# HeartAware_Main.net
KiCad netlist of a schematic drawn in Altium Designer
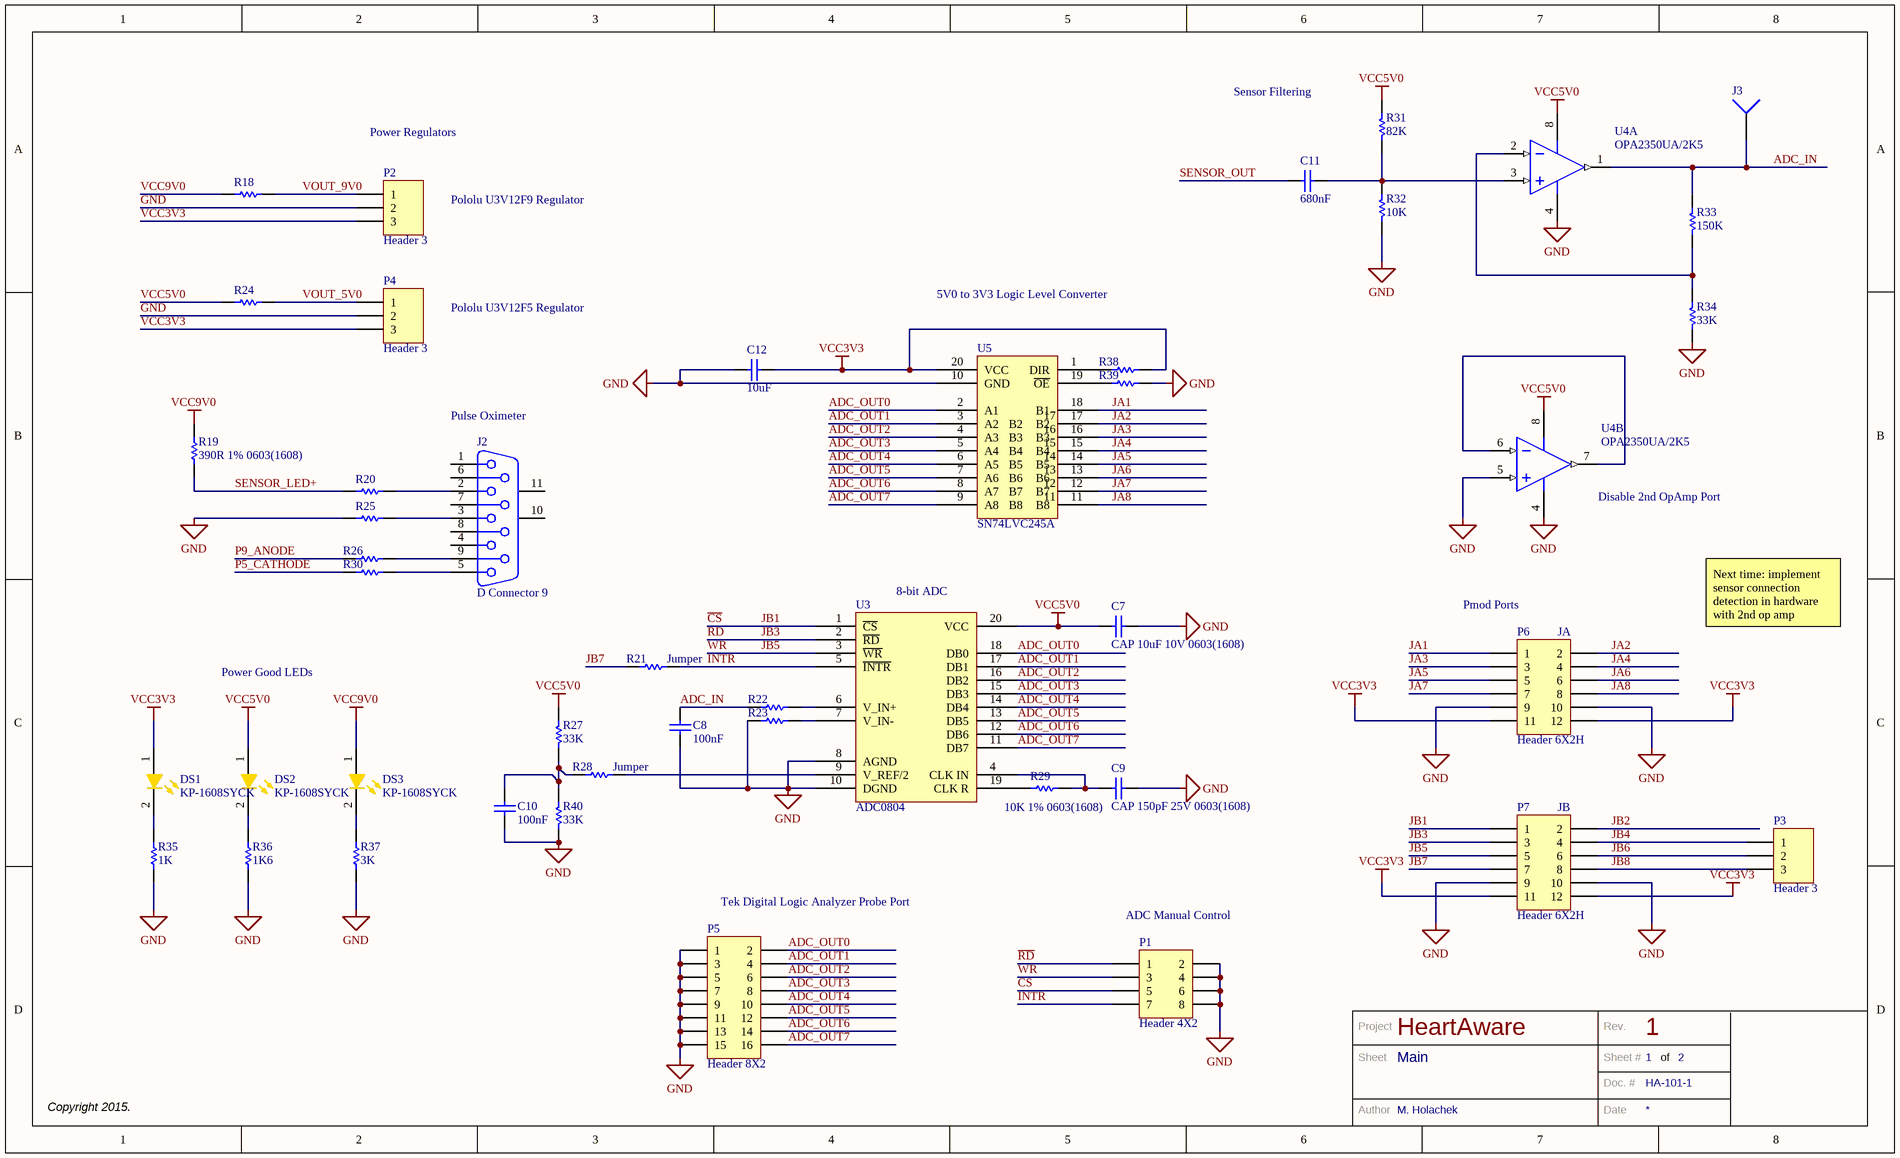
[diagram p0: HeartAware_Main.SchDoc]

(export (version "E")
  (design (tool "Eeschema 10.0.6"))
  (components
    (comp (ref "C7")
      (value "CAP 10uF 10V 0603(1608)")
      (footprint "CAPC0603(1608)100_N")
      (description "CAP 10uF 10V Â±10% 0603 (1608 Metric) Thickness 1mm SMD")
      (fields (field (name "TOLERANCE") "Â±10%"))
      (libsource (lib "Altium Content Vault") (part "CAP"))
    )
    (comp (ref "C8")
      (value "100nF")
      (footprint "CAPC0603(1608)100_M")
      (description "CAP 100nF 25V Â±10% 0603 (1608 Metric) Thickness 1mm SMD")
      (fields (field (name "TOLERANCE") "Â±10%"))
      (libsource (lib "Altium Content Vault") (part "CMP-1035-02588-1"))
    )
    (comp (ref "C9")
      (value "CAP 150pF 25V 0603(1608)")
      (footprint "CAPC0603(1608)100_L")
      (description "CAP 150pF 25V Â±2% 0603 (1608 Metric) Thickness 1mm SMD")
      (fields (field (name "TOLERANCE") "Â±2%"))
      (libsource (lib "Altium Content Vault") (part "CAP"))
    )
    (comp (ref "C10")
      (value "100nF")
      (footprint "CAPC0603(1608)100_M")
      (description "CAP 100nF 25V Â±10% 0603 (1608 Metric) Thickness 1mm SMD")
      (fields (field (name "TOLERANCE") "Â±10%"))
      (libsource (lib "Altium Content Vault") (part "CMP-1035-02588-1"))
    )
    (comp (ref "C11")
      (value "680nF")
      (footprint "CAPC0603(1608)100_N")
      (description "CAP 680nF 25V Â±10% 0603 (1608 Metric) Thickness 1mm SMD")
      (fields (field (name "TOLERANCE") "Â±10%"))
      (libsource (lib "Altium Content Vault") (part "CMP-1035-02722-1"))
    )
    (comp (ref "C12")
      (value "10uF")
      (footprint "CAPC0603(1608)100_N")
      (description "CAP 10uF 10V Â±10% 0603 (1608 Metric) Thickness 1mm SMD")
      (fields (field (name "TOLERANCE") "Â±10%"))
      (libsource (lib "Altium Content Vault") (part "CMP-1035-02799-1"))
    )
    (comp (ref "DS1")
      (value "KP-1608SYCK")
      (footprint "KING-0603LED_YELLOW_V")
      (description "LED, SMT, 0603(1608), 1.1mm thickness, Yellow")
      (fields (field (name "MANUFACTURER") "Kingbright"))
      (libsource (lib "Altium Content Vault") (part "KING-LED-YELLOW-A1K2-2"))
    )
    (comp (ref "DS2")
      (value "KP-1608SYCK")
      (footprint "KING-0603LED_YELLOW_V")
      (description "LED, SMT, 0603(1608), 1.1mm thickness, Yellow")
      (fields (field (name "MANUFACTURER") "Kingbright"))
      (libsource (lib "Altium Content Vault") (part "KING-LED-YELLOW-A1K2-2"))
    )
    (comp (ref "DS3")
      (value "KP-1608SYCK")
      (footprint "KING-0603LED_YELLOW_V")
      (description "LED, SMT, 0603(1608), 1.1mm thickness, Yellow")
      (fields (field (name "MANUFACTURER") "Kingbright"))
      (libsource (lib "Altium Content Vault") (part "KING-LED-YELLOW-A1K2-2"))
    )
    (comp (ref "J2")
      (value "D Connector 9")
      (footprint "DSUB1.385-2H9")
      (description "Receptacle Assembly, 9 Position, Right Angle")
      (fields (field (name "PUBLISHER") "Altium Limited"))
      (libsource (lib "Miscellaneous Connectors") (part "D Connector 9"))
    )
    (comp (ref "J3")
      (value "Socket")
      (footprint "PIN1")
      (fields (field (name "PUBLISHER") "Altium Limited"))
      (libsource (lib "Miscellaneous Connectors") (part "Socket"))
    )
    (comp (ref "P1")
      (value "Header 4X2")
      (footprint "HDR2X4")
      (description "Header, 4-Pin, Dual row")
      (fields (field (name "PUBLISHER") "Altium Limited"))
      (libsource (lib "Miscellaneous Connectors") (part "Header 4X2"))
    )
    (comp (ref "P2")
      (value "Header 3")
      (footprint "HDR1X3")
      (description "Header, 3-Pin")
      (fields (field (name "PUBLISHER") "Altium Limited"))
      (libsource (lib "Miscellaneous Connectors") (part "Header 3"))
    )
    (comp (ref "P3")
      (value "Header 3")
      (footprint "HDR1X3")
      (description "Header, 3-Pin")
      (fields (field (name "PUBLISHER") "Altium Limited"))
      (libsource (lib "Miscellaneous Connectors") (part "Header 3"))
    )
    (comp (ref "P4")
      (value "Header 3")
      (footprint "HDR1X3")
      (description "Header, 3-Pin")
      (fields (field (name "PUBLISHER") "Altium Limited"))
      (libsource (lib "Miscellaneous Connectors") (part "Header 3"))
    )
    (comp (ref "P5")
      (value "Header 8X2")
      (footprint "HDR2X8")
      (description "Header, 8-Pin, Dual row")
      (fields (field (name "PUBLISHER") "Altium Limited"))
      (libsource (lib "Miscellaneous Connectors") (part "Header 8X2"))
    )
    (comp (ref "P6")
      (value "Header 6X2H")
      (footprint "HDR2X6H")
      (description "Header, 6-Pin, Dual row, Right Angle")
      (fields (field (name "PUBLISHER") "Altium Limited"))
      (libsource (lib "Miscellaneous Connectors") (part "Header 6X2H"))
    )
    (comp (ref "P7")
      (value "Header 6X2H")
      (footprint "HDR2X6H")
      (description "Header, 6-Pin, Dual row, Right Angle")
      (fields (field (name "PUBLISHER") "Altium Limited"))
      (libsource (lib "Miscellaneous Connectors") (part "Header 6X2H"))
    )
    (comp (ref "R18")
      (value "Jumper 0603(1608)")
      (footprint "RESC0603(1608)_N")
      (description "Jumper 0603 (1608 Metric)")
      (fields (field (name "POWER") "None"))
      (libsource (lib "Altium Content Vault") (part "RES"))
    )
    (comp (ref "R19")
      (value "390R 1% 0603(1608)")
      (footprint "RESC0603(1608)_L")
      (description "390R 0.1W 1% 0603 (1608 Metric)  SMD")
      (fields (field (name "POWER") "0.1 W") (field (name "TOLERANCE") "1 %"))
      (libsource (lib "Altium Content Vault") (part "RES"))
    )
    (comp (ref "R20")
      (value "Jumper 0603(1608)")
      (footprint "RESC0603(1608)_M")
      (description "Jumper 0603 (1608 Metric)")
      (fields (field (name "POWER") "None"))
      (libsource (lib "Altium Content Vault") (part "CMP-1012-00001-1"))
    )
    (comp (ref "R21")
      (value "Jumper")
      (footprint "RESC0603(1608)_N")
      (description "Jumper 0603 (1608 Metric)")
      (fields (field (name "POWER") "None"))
      (libsource (lib "Altium Content Vault") (part "RES"))
    )
    (comp (ref "R22")
      (value "Jumper")
      (footprint "RESC0603(1608)_N")
      (description "Jumper 0603 (1608 Metric)")
      (fields (field (name "POWER") "None"))
      (libsource (lib "Altium Content Vault") (part "CMP-1012-00001-1"))
    )
    (comp (ref "R23")
      (value "Jumper")
      (footprint "RESC0603(1608)_N")
      (description "Jumper 0603 (1608 Metric)")
      (fields (field (name "POWER") "None"))
      (libsource (lib "Altium Content Vault") (part "CMP-1012-00001-1"))
    )
    (comp (ref "R24")
      (value "Jumper 0603(1608)")
      (footprint "RESC0603(1608)_N")
      (description "Jumper 0603 (1608 Metric)")
      (fields (field (name "POWER") "None"))
      (libsource (lib "Altium Content Vault") (part "RES"))
    )
    (comp (ref "R25")
      (value "Jumper 0603(1608)")
      (footprint "RESC0603(1608)_M")
      (description "Jumper 0603 (1608 Metric)")
      (fields (field (name "POWER") "None"))
      (libsource (lib "Altium Content Vault") (part "CMP-1012-00001-1"))
    )
    (comp (ref "R26")
      (value "Jumper 0603(1608)")
      (footprint "RESC0603(1608)_M")
      (description "Jumper 0603 (1608 Metric)")
      (fields (field (name "POWER") "None"))
      (libsource (lib "Altium Content Vault") (part "RES"))
    )
    (comp (ref "R27")
      (value "33K")
      (footprint "RESC0603(1608)_N")
      (description "33K 0.1W 1% 0603 (1608 Metric)  SMD")
      (fields (field (name "TOLERANCE") "1 %") (field (name "POWER") "0.1 W"))
      (libsource (lib "Altium Content Vault") (part "CMP-1012-00680-1"))
    )
    (comp (ref "R28")
      (value "Jumper")
      (footprint "RESC0603(1608)_N")
      (description "Jumper 0603 (1608 Metric)")
      (fields (field (name "POWER") "None"))
      (libsource (lib "Altium Content Vault") (part "RES"))
    )
    (comp (ref "R29")
      (value "10K 1% 0603(1608)")
      (footprint "RESC0603(1608)_N")
      (description "10K 0.1W 1% 0603 (1608 Metric)  SMD")
      (fields (field (name "POWER") "0.1 W") (field (name "TOLERANCE") "1 %"))
      (libsource (lib "Altium Content Vault") (part "RES"))
    )
    (comp (ref "R30")
      (value "Jumper 0603(1608)")
      (footprint "RESC0603(1608)_M")
      (description "Jumper 0603 (1608 Metric)")
      (fields (field (name "POWER") "None"))
      (libsource (lib "Altium Content Vault") (part "CMP-1012-00001-1"))
    )
    (comp (ref "R31")
      (value "82K")
      (footprint "RESC0603(1608)_N")
      (description "82K 0.1W 1% 0603 (1608 Metric)  SMD")
      (fields (field (name "TOLERANCE") "1 %") (field (name "POWER") "0.1 W"))
      (libsource (lib "Altium Content Vault") (part "CMP-1012-00726-1"))
    )
    (comp (ref "R32")
      (value "10K")
      (footprint "RESC0603(1608)_N")
      (description "10K 0.1W 1% 0603 (1608 Metric)  SMD")
      (fields (field (name "POWER") "0.1 W") (field (name "TOLERANCE") "1 %"))
      (libsource (lib "Altium Content Vault") (part "CMP-1012-00623-1"))
    )
    (comp (ref "R33")
      (value "150K")
      (footprint "RESC0603(1608)_L")
      (description "150K 0.1W 1% 0603 (1608 Metric)  SMD")
      (fields (field (name "TOLERANCE") "1 %") (field (name "POWER") "0.1 W"))
      (libsource (lib "Altium Content Vault") (part "CMP-1012-00754-1"))
    )
    (comp (ref "R34")
      (value "33K")
      (footprint "RESC0603(1608)_N")
      (description "33K 0.1W 1% 0603 (1608 Metric)  SMD")
      (fields (field (name "TOLERANCE") "1 %") (field (name "POWER") "0.1 W"))
      (libsource (lib "Altium Content Vault") (part "CMP-1012-00680-1"))
    )
    (comp (ref "R35")
      (value "1K")
      (footprint "RESC0603(1608)_M")
      (description "1K 0.1W 1% 0603 (1608 Metric)  SMD")
      (fields (field (name "TOLERANCE") "1 %") (field (name "POWER") "0.1 W"))
      (libsource (lib "Altium Content Vault") (part "RES"))
    )
    (comp (ref "R36")
      (value "1K6")
      (footprint "RESC0603(1608)_L")
      (description "1K6 0.1W 1% 0603 (1608 Metric)  SMD")
      (fields (field (name "TOLERANCE") "1 %") (field (name "POWER") "0.1 W"))
      (libsource (lib "Altium Content Vault") (part "CMP-1012-00531-1"))
    )
    (comp (ref "R37")
      (value "3K")
      (footprint "RESC0603(1608)_N")
      (description "3K 0.1W 1% 0603 (1608 Metric)  SMD")
      (fields (field (name "POWER") "0.1 W") (field (name "TOLERANCE") "1 %"))
      (libsource (lib "Altium Content Vault") (part "CMP-1012-00562-1"))
    )
    (comp (ref "R38")
      (value "Jumper 0603(1608)")
      (footprint "RESC0603(1608)_N")
      (description "Jumper 0603 (1608 Metric)")
      (fields (field (name "POWER") "None"))
      (libsource (lib "Altium Content Vault") (part "RES"))
    )
    (comp (ref "R39")
      (value "Jumper 0603(1608)")
      (footprint "RESC0603(1608)_N")
      (description "Jumper 0603 (1608 Metric)")
      (fields (field (name "POWER") "None"))
      (libsource (lib "Altium Content Vault") (part "RES"))
    )
    (comp (ref "R40")
      (value "33K")
      (footprint "RESC0603(1608)_N")
      (description "33K 0.1W 1% 0603 (1608 Metric)  SMD")
      (fields (field (name "TOLERANCE") "1 %") (field (name "POWER") "0.1 W"))
      (libsource (lib "Altium Content Vault") (part "CMP-1012-00680-1"))
    )
    (comp (ref "U3")
      (value "ADC0804")
      (footprint "SOIC127P1030X265-20N")
      (description "8-Bit Parallel Analog-to-Digital Converter")
      (libsource (lib "IC") (part "ADC0804"))
    )
    (comp (ref "U4")
      (value "OPA2350UA/2K5")
      (footprint "TI-D8_M")
      (fields (field (name "MANUFACTURER") "Texas Instruments"))
      (libsource (lib "Altium Content Vault") (part "TI-OPA-8_2"))
    )
    (comp (ref "U5")
      (value "SN74LVC245A")
      (footprint "SOIC127P780X200-20N")
      (description "Octal Bus Tranceiver With 3-State Outputs")
      (libsource (lib "IC") (part "SN74LVC245A"))
    )
  )
  (nets
    (net (code "1") (name "/ADC_IN") (class "Default")
      (node (ref "C8") (pin "2") (pinfunction "2_2") (pintype "passive"))
      (node (ref "J3") (pin "1") (pinfunction "1_1") (pintype "passive"))
      (node (ref "R22") (pin "1") (pinfunction "1_1") (pintype "passive"))
      (node (ref "R33") (pin "1") (pinfunction "1_1") (pintype "passive"))
      (node (ref "U4") (pin "1") (pinfunction "OUT_A_1") (pintype "output"))
    )
    (net (code "2") (name "/ADC_OUT0") (class "Default")
      (node (ref "P5") (pin "2") (pinfunction "2_2") (pintype "passive"))
      (node (ref "U3") (pin "18") (pinfunction "DB0_18") (pintype "passive"))
      (node (ref "U5") (pin "2") (pinfunction "A1_2") (pintype "passive"))
    )
    (net (code "3") (name "/ADC_OUT1") (class "Default")
      (node (ref "P5") (pin "4") (pinfunction "4_4") (pintype "passive"))
      (node (ref "U3") (pin "17") (pinfunction "DB1_17") (pintype "passive"))
      (node (ref "U5") (pin "3") (pinfunction "A2_3") (pintype "passive"))
    )
    (net (code "4") (name "/ADC_OUT2") (class "Default")
      (node (ref "P5") (pin "6") (pinfunction "6_6") (pintype "passive"))
      (node (ref "U3") (pin "16") (pinfunction "DB2_16") (pintype "passive"))
      (node (ref "U5") (pin "4") (pinfunction "A3_4") (pintype "passive"))
    )
    (net (code "5") (name "/ADC_OUT3") (class "Default")
      (node (ref "P5") (pin "8") (pinfunction "8_8") (pintype "passive"))
      (node (ref "U3") (pin "15") (pinfunction "DB3_15") (pintype "passive"))
      (node (ref "U5") (pin "5") (pinfunction "A4_5") (pintype "passive"))
    )
    (net (code "6") (name "/ADC_OUT4") (class "Default")
      (node (ref "P5") (pin "10") (pinfunction "10_10") (pintype "passive"))
      (node (ref "U3") (pin "14") (pinfunction "DB4_14") (pintype "passive"))
      (node (ref "U5") (pin "6") (pinfunction "A5_6") (pintype "passive"))
    )
    (net (code "7") (name "/ADC_OUT5") (class "Default")
      (node (ref "P5") (pin "12") (pinfunction "12_12") (pintype "passive"))
      (node (ref "U3") (pin "13") (pinfunction "DB5_13") (pintype "passive"))
      (node (ref "U5") (pin "7") (pinfunction "A6_7") (pintype "passive"))
    )
    (net (code "8") (name "/ADC_OUT6") (class "Default")
      (node (ref "P5") (pin "14") (pinfunction "14_14") (pintype "passive"))
      (node (ref "U3") (pin "12") (pinfunction "DB6_12") (pintype "passive"))
      (node (ref "U5") (pin "8") (pinfunction "A7_8") (pintype "passive"))
    )
    (net (code "9") (name "/ADC_OUT7") (class "Default")
      (node (ref "P5") (pin "16") (pinfunction "16_16") (pintype "passive"))
      (node (ref "U3") (pin "11") (pinfunction "DB7_11") (pintype "passive"))
      (node (ref "U5") (pin "9") (pinfunction "A8_9") (pintype "passive"))
    )
    (net (code "10") (name "/CS") (class "Default")
      (node (ref "P1") (pin "5") (pinfunction "5_5") (pintype "passive"))
      (node (ref "P7") (pin "1") (pinfunction "1_1") (pintype "passive"))
      (node (ref "U3") (pin "1") (pinfunction "CS_1") (pintype "passive"))
    )
    (net (code "11") (name "/INTR") (class "Default")
      (node (ref "P1") (pin "7") (pinfunction "7_7") (pintype "passive"))
      (node (ref "R21") (pin "2") (pinfunction "2_2") (pintype "passive"))
      (node (ref "U3") (pin "5") (pinfunction "INTR_5") (pintype "passive"))
    )
    (net (code "12") (name "/JA1") (class "Default")
      (node (ref "P6") (pin "1") (pinfunction "1_1") (pintype "passive"))
      (node (ref "U5") (pin "18") (pinfunction "B1_18") (pintype "passive"))
    )
    (net (code "13") (name "/JA2") (class "Default")
      (node (ref "P6") (pin "2") (pinfunction "2_2") (pintype "passive"))
      (node (ref "U5") (pin "17") (pinfunction "B2_17") (pintype "passive"))
    )
    (net (code "14") (name "/JA3") (class "Default")
      (node (ref "P6") (pin "3") (pinfunction "3_3") (pintype "passive"))
      (node (ref "U5") (pin "16") (pinfunction "B3_16") (pintype "passive"))
    )
    (net (code "15") (name "/JA4") (class "Default")
      (node (ref "P6") (pin "4") (pinfunction "4_4") (pintype "passive"))
      (node (ref "U5") (pin "15") (pinfunction "B4_15") (pintype "passive"))
    )
    (net (code "16") (name "/JA5") (class "Default")
      (node (ref "P6") (pin "5") (pinfunction "5_5") (pintype "passive"))
      (node (ref "U5") (pin "14") (pinfunction "B5_14") (pintype "passive"))
    )
    (net (code "17") (name "/JA6") (class "Default")
      (node (ref "P6") (pin "6") (pinfunction "6_6") (pintype "passive"))
      (node (ref "U5") (pin "13") (pinfunction "B6_13") (pintype "passive"))
    )
    (net (code "18") (name "/JA7") (class "Default")
      (node (ref "P6") (pin "7") (pinfunction "7_7") (pintype "passive"))
      (node (ref "U5") (pin "12") (pinfunction "B7_12") (pintype "passive"))
    )
    (net (code "19") (name "/JA8") (class "Default")
      (node (ref "P6") (pin "8") (pinfunction "8_8") (pintype "passive"))
      (node (ref "U5") (pin "11") (pinfunction "B8_11") (pintype "passive"))
    )
    (net (code "20") (name "/JB2") (class "Default")
      (node (ref "P7") (pin "2") (pinfunction "2_2") (pintype "passive"))
    )
    (net (code "21") (name "/JB3") (class "Default")
      (node (ref "P1") (pin "1") (pinfunction "1_1") (pintype "passive"))
      (node (ref "P7") (pin "3") (pinfunction "3_3") (pintype "passive"))
      (node (ref "U3") (pin "2") (pinfunction "RD_2") (pintype "passive"))
    )
    (net (code "22") (name "/JB4") (class "Default")
      (node (ref "P3") (pin "1") (pinfunction "1_1") (pintype "passive"))
      (node (ref "P7") (pin "4") (pinfunction "4_4") (pintype "passive"))
    )
    (net (code "23") (name "/JB5") (class "Default")
      (node (ref "P1") (pin "3") (pinfunction "3_3") (pintype "passive"))
      (node (ref "P7") (pin "5") (pinfunction "5_5") (pintype "passive"))
      (node (ref "U3") (pin "3") (pinfunction "WR_3") (pintype "passive"))
    )
    (net (code "24") (name "/JB6") (class "Default")
      (node (ref "P3") (pin "2") (pinfunction "2_2") (pintype "passive"))
      (node (ref "P7") (pin "6") (pinfunction "6_6") (pintype "passive"))
    )
    (net (code "25") (name "/JB7") (class "Default")
      (node (ref "P7") (pin "7") (pinfunction "7_7") (pintype "passive"))
      (node (ref "R21") (pin "1") (pinfunction "1_1") (pintype "passive"))
    )
    (net (code "26") (name "/JB8") (class "Default")
      (node (ref "P3") (pin "3") (pinfunction "3_3") (pintype "passive"))
      (node (ref "P7") (pin "8") (pinfunction "8_8") (pintype "passive"))
    )
    (net (code "27") (name "/P5_CATHODE") (class "Default")
      (node (ref "R30") (pin "1") (pinfunction "1_1") (pintype "passive"))
    )
    (net (code "28") (name "/P9_ANODE") (class "Default")
      (node (ref "R26") (pin "1") (pinfunction "1_1") (pintype "passive"))
    )
    (net (code "29") (name "/SENSOR_LED+") (class "Default")
      (node (ref "R19") (pin "1") (pinfunction "1_1") (pintype "passive"))
      (node (ref "R20") (pin "1") (pinfunction "1_1") (pintype "passive"))
    )
    (net (code "30") (name "/SENSOR_OUT") (class "Default")
      (node (ref "C11") (pin "1") (pinfunction "1_1") (pintype "passive"))
    )
    (net (code "31") (name "/VOUT_5V0") (class "Default")
      (node (ref "P4") (pin "1") (pinfunction "1_1") (pintype "passive"))
      (node (ref "R24") (pin "2") (pinfunction "2_2") (pintype "passive"))
    )
    (net (code "32") (name "/VOUT_9V0") (class "Default")
      (node (ref "P2") (pin "1") (pinfunction "1_1") (pintype "passive"))
      (node (ref "R18") (pin "2") (pinfunction "2_2") (pintype "passive"))
    )
    (net (code "33") (name "GND") (class "Default")
      (node (ref "C10") (pin "1") (pinfunction "1_1") (pintype "passive"))
      (node (ref "C12") (pin "2") (pinfunction "2_2") (pintype "passive"))
      (node (ref "C7") (pin "1") (pinfunction "1_1") (pintype "passive"))
      (node (ref "C8") (pin "1") (pinfunction "1_1") (pintype "passive"))
      (node (ref "C9") (pin "2") (pinfunction "2_2") (pintype "passive"))
      (node (ref "P1") (pin "2") (pinfunction "2_2") (pintype "passive"))
      (node (ref "P1") (pin "4") (pinfunction "4_4") (pintype "passive"))
      (node (ref "P1") (pin "6") (pinfunction "6_6") (pintype "passive"))
      (node (ref "P1") (pin "8") (pinfunction "8_8") (pintype "passive"))
      (node (ref "P2") (pin "2") (pinfunction "2_2") (pintype "passive"))
      (node (ref "P4") (pin "2") (pinfunction "2_2") (pintype "passive"))
      (node (ref "P5") (pin "1") (pinfunction "1_1") (pintype "passive"))
      (node (ref "P5") (pin "11") (pinfunction "11_11") (pintype "passive"))
      (node (ref "P5") (pin "13") (pinfunction "13_13") (pintype "passive"))
      (node (ref "P5") (pin "15") (pinfunction "15_15") (pintype "passive"))
      (node (ref "P5") (pin "3") (pinfunction "3_3") (pintype "passive"))
      (node (ref "P5") (pin "5") (pinfunction "5_5") (pintype "passive"))
      (node (ref "P5") (pin "7") (pinfunction "7_7") (pintype "passive"))
      (node (ref "P5") (pin "9") (pinfunction "9_9") (pintype "passive"))
      (node (ref "P6") (pin "10") (pinfunction "10_10") (pintype "passive"))
      (node (ref "P6") (pin "9") (pinfunction "9_9") (pintype "passive"))
      (node (ref "P7") (pin "10") (pinfunction "10_10") (pintype "passive"))
      (node (ref "P7") (pin "9") (pinfunction "9_9") (pintype "passive"))
      (node (ref "R23") (pin "1") (pinfunction "1_1") (pintype "passive"))
      (node (ref "R25") (pin "1") (pinfunction "1_1") (pintype "passive"))
      (node (ref "R32") (pin "2") (pinfunction "2_2") (pintype "passive"))
      (node (ref "R34") (pin "2") (pinfunction "2_2") (pintype "passive"))
      (node (ref "R35") (pin "1") (pinfunction "1_1") (pintype "passive"))
      (node (ref "R36") (pin "1") (pinfunction "1_1") (pintype "passive"))
      (node (ref "R37") (pin "1") (pinfunction "1_1") (pintype "passive"))
      (node (ref "R39") (pin "2") (pinfunction "2_2") (pintype "passive"))
      (node (ref "R40") (pin "2") (pinfunction "2_2") (pintype "passive"))
      (node (ref "U3") (pin "10") (pinfunction "DGND_10") (pintype "passive"))
      (node (ref "U3") (pin "8") (pinfunction "AGND_8") (pintype "passive"))
      (node (ref "U4") (pin "4") (pinfunction "V-_4") (pintype "power_in"))
      (node (ref "U4") (pin "5") (pinfunction "IN_B+_5") (pintype "input"))
      (node (ref "U5") (pin "10") (pinfunction "GND_10") (pintype "passive"))
    )
    (net (code "34") (name "Net-(C10-Pad2)") (class "Default")
      (node (ref "C10") (pin "2") (pinfunction "2_2") (pintype "passive"))
      (node (ref "R27") (pin "2") (pinfunction "2_2") (pintype "passive"))
      (node (ref "R28") (pin "1") (pinfunction "1_1") (pintype "passive"))
      (node (ref "R40") (pin "1") (pinfunction "1_1") (pintype "passive"))
    )
    (net (code "35") (name "Net-(DS1-K)") (class "Default")
      (node (ref "DS1") (pin "2") (pinfunction "K_2") (pintype "passive"))
      (node (ref "R35") (pin "2") (pinfunction "2_2") (pintype "passive"))
    )
    (net (code "36") (name "Net-(DS2-K)") (class "Default")
      (node (ref "DS2") (pin "2") (pinfunction "K_2") (pintype "passive"))
      (node (ref "R36") (pin "2") (pinfunction "2_2") (pintype "passive"))
    )
    (net (code "37") (name "Net-(DS3-K)") (class "Default")
      (node (ref "DS3") (pin "2") (pinfunction "K_2") (pintype "passive"))
      (node (ref "R37") (pin "2") (pinfunction "2_2") (pintype "passive"))
    )
    (net (code "38") (name "Net-(J2-Pad2)") (class "Default")
      (node (ref "J2") (pin "2") (pinfunction "2_2") (pintype "passive"))
      (node (ref "R20") (pin "2") (pinfunction "2_2") (pintype "passive"))
    )
    (net (code "39") (name "Net-(J2-Pad3)") (class "Default")
      (node (ref "J2") (pin "3") (pinfunction "3_3") (pintype "passive"))
      (node (ref "R25") (pin "2") (pinfunction "2_2") (pintype "passive"))
    )
    (net (code "40") (name "Net-(J2-Pad5)") (class "Default")
      (node (ref "J2") (pin "5") (pinfunction "5_5") (pintype "passive"))
      (node (ref "R30") (pin "2") (pinfunction "2_2") (pintype "passive"))
    )
    (net (code "41") (name "Net-(J2-Pad9)") (class "Default")
      (node (ref "J2") (pin "9") (pinfunction "9_9") (pintype "passive"))
      (node (ref "R26") (pin "2") (pinfunction "2_2") (pintype "passive"))
    )
    (net (code "42") (name "Net-(U3-CLK_IN)") (class "Default")
      (node (ref "C9") (pin "1") (pinfunction "1_1") (pintype "passive"))
      (node (ref "R29") (pin "2") (pinfunction "2_2") (pintype "passive"))
      (node (ref "U3") (pin "4") (pinfunction "CLK_IN_4") (pintype "passive"))
    )
    (net (code "43") (name "Net-(U3-CLK_R)") (class "Default")
      (node (ref "R29") (pin "1") (pinfunction "1_1") (pintype "passive"))
      (node (ref "U3") (pin "19") (pinfunction "CLK_R_19") (pintype "passive"))
    )
    (net (code "44") (name "Net-(U3-V_IN+)") (class "Default")
      (node (ref "R22") (pin "2") (pinfunction "2_2") (pintype "passive"))
      (node (ref "U3") (pin "6") (pinfunction "V_IN+_6") (pintype "passive"))
    )
    (net (code "45") (name "Net-(U3-V_IN-)") (class "Default")
      (node (ref "R23") (pin "2") (pinfunction "2_2") (pintype "passive"))
      (node (ref "U3") (pin "7") (pinfunction "V_IN-_7") (pintype "passive"))
    )
    (net (code "46") (name "Net-(U3-V_REF{slash}2)") (class "Default")
      (node (ref "R28") (pin "2") (pinfunction "2_2") (pintype "passive"))
      (node (ref "U3") (pin "9") (pinfunction "V_REF/2_9") (pintype "passive"))
    )
    (net (code "47") (name "Net-(U4A-IN_A+)") (class "Default")
      (node (ref "C11") (pin "2") (pinfunction "2_2") (pintype "passive"))
      (node (ref "R31") (pin "2") (pinfunction "2_2") (pintype "passive"))
      (node (ref "R32") (pin "1") (pinfunction "1_1") (pintype "passive"))
      (node (ref "U4") (pin "3") (pinfunction "IN_A+_3") (pintype "input"))
    )
    (net (code "48") (name "Net-(U4A-IN_A-)") (class "Default")
      (node (ref "R33") (pin "2") (pinfunction "2_2") (pintype "passive"))
      (node (ref "R34") (pin "1") (pinfunction "1_1") (pintype "passive"))
      (node (ref "U4") (pin "2") (pinfunction "IN_A-_2") (pintype "input"))
    )
    (net (code "49") (name "Net-(U4B-IN_B-)") (class "Default")
      (node (ref "U4") (pin "6") (pinfunction "IN_B-_6") (pintype "input"))
      (node (ref "U4") (pin "7") (pinfunction "OUT_B_7") (pintype "output"))
    )
    (net (code "50") (name "Net-(U5-DIR)") (class "Default")
      (node (ref "R38") (pin "1") (pinfunction "1_1") (pintype "passive"))
      (node (ref "U5") (pin "1") (pinfunction "DIR_1") (pintype "passive"))
    )
    (net (code "51") (name "Net-(U5-OE)") (class "Default")
      (node (ref "R39") (pin "1") (pinfunction "1_1") (pintype "passive"))
      (node (ref "U5") (pin "19") (pinfunction "OE_19") (pintype "passive"))
    )
    (net (code "52") (name "VCC3V3") (class "Default")
      (node (ref "C12") (pin "1") (pinfunction "1_1") (pintype "passive"))
      (node (ref "DS1") (pin "1") (pinfunction "A_1") (pintype "passive"))
      (node (ref "P2") (pin "3") (pinfunction "3_3") (pintype "passive"))
      (node (ref "P4") (pin "3") (pinfunction "3_3") (pintype "passive"))
      (node (ref "P6") (pin "11") (pinfunction "11_11") (pintype "passive"))
      (node (ref "P6") (pin "12") (pinfunction "12_12") (pintype "passive"))
      (node (ref "P7") (pin "11") (pinfunction "11_11") (pintype "passive"))
      (node (ref "P7") (pin "12") (pinfunction "12_12") (pintype "passive"))
      (node (ref "R38") (pin "2") (pinfunction "2_2") (pintype "passive"))
      (node (ref "U5") (pin "20") (pinfunction "VCC_20") (pintype "passive"))
    )
    (net (code "53") (name "VCC5V0") (class "Default")
      (node (ref "C7") (pin "2") (pinfunction "2_2") (pintype "passive"))
      (node (ref "DS2") (pin "1") (pinfunction "A_1") (pintype "passive"))
      (node (ref "R24") (pin "1") (pinfunction "1_1") (pintype "passive"))
      (node (ref "R27") (pin "1") (pinfunction "1_1") (pintype "passive"))
      (node (ref "R31") (pin "1") (pinfunction "1_1") (pintype "passive"))
      (node (ref "U3") (pin "20") (pinfunction "VCC_20") (pintype "passive"))
      (node (ref "U4") (pin "8") (pinfunction "V+_8") (pintype "power_in"))
    )
    (net (code "54") (name "VCC9V0") (class "Default")
      (node (ref "DS3") (pin "1") (pinfunction "A_1") (pintype "passive"))
      (node (ref "R18") (pin "1") (pinfunction "1_1") (pintype "passive"))
      (node (ref "R19") (pin "2") (pinfunction "2_2") (pintype "passive"))
    )
    (net (code "55") (name "unconnected-(J2-MH1-Pad10)") (class "Default")
      (node (ref "J2") (pin "10") (pinfunction "MH1_10") (pintype "passive"))
    )
    (net (code "56") (name "unconnected-(J2-MH2-Pad11)") (class "Default")
      (node (ref "J2") (pin "11") (pinfunction "MH2_11") (pintype "passive"))
    )
    (net (code "57") (name "unconnected-(J2-Pad1)") (class "Default")
      (node (ref "J2") (pin "1") (pinfunction "1_1") (pintype "passive"))
    )
    (net (code "58") (name "unconnected-(J2-Pad4)") (class "Default")
      (node (ref "J2") (pin "4") (pinfunction "4_4") (pintype "passive"))
    )
    (net (code "59") (name "unconnected-(J2-Pad6)") (class "Default")
      (node (ref "J2") (pin "6") (pinfunction "6_6") (pintype "passive"))
    )
    (net (code "60") (name "unconnected-(J2-Pad7)") (class "Default")
      (node (ref "J2") (pin "7") (pinfunction "7_7") (pintype "passive"))
    )
    (net (code "61") (name "unconnected-(J2-Pad8)") (class "Default")
      (node (ref "J2") (pin "8") (pinfunction "8_8") (pintype "passive"))
    )
    (net (code "62") (name "unconnected-(U5-B2-Pad17)") (class "Default")
      (node (ref "U5") (pin "17") (pinfunction "B2_17") (pintype "passive"))
    )
    (net (code "63") (name "unconnected-(U5-B3-Pad16)") (class "Default")
      (node (ref "U5") (pin "16") (pinfunction "B3_16") (pintype "passive"))
    )
    (net (code "64") (name "unconnected-(U5-B4-Pad15)") (class "Default")
      (node (ref "U5") (pin "15") (pinfunction "B4_15") (pintype "passive"))
    )
    (net (code "65") (name "unconnected-(U5-B5-Pad14)") (class "Default")
      (node (ref "U5") (pin "14") (pinfunction "B5_14") (pintype "passive"))
    )
    (net (code "66") (name "unconnected-(U5-B6-Pad13)") (class "Default")
      (node (ref "U5") (pin "13") (pinfunction "B6_13") (pintype "passive"))
    )
    (net (code "67") (name "unconnected-(U5-B7-Pad12)") (class "Default")
      (node (ref "U5") (pin "12") (pinfunction "B7_12") (pintype "passive"))
    )
    (net (code "68") (name "unconnected-(U5-B8-Pad11)") (class "Default")
      (node (ref "U5") (pin "11") (pinfunction "B8_11") (pintype "passive"))
    )
  )
)
